# Main_PCB.net
KiCad netlist of a schematic drawn in EAGLE
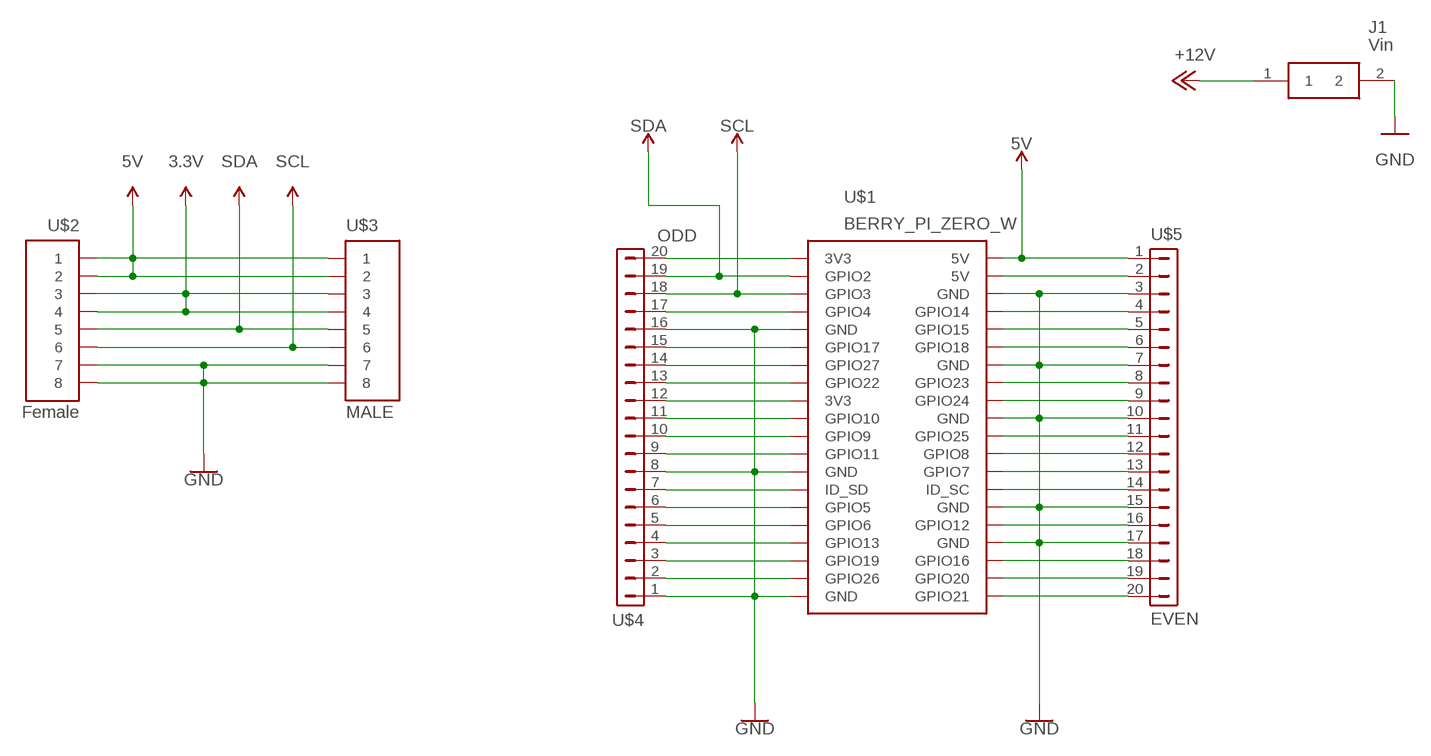
[diagram p0: schematic, sheet 1]
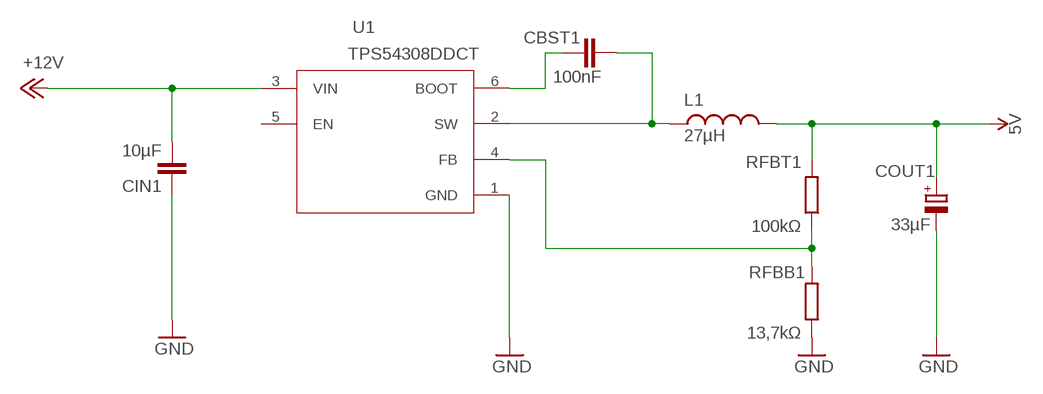
[diagram p1: schematic, sheet 2]
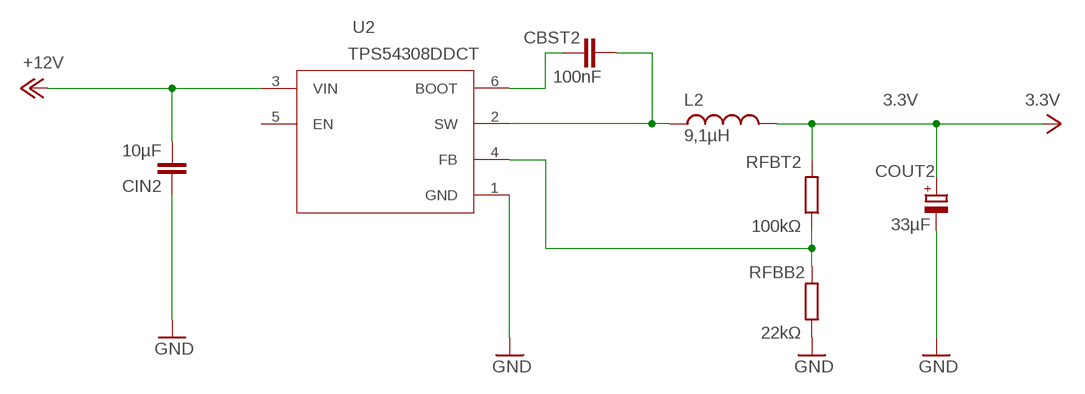
[diagram p2: schematic, sheet 3]

(export (version "E")
  (design (tool "Eeschema 10.0.6"))
  (components
    (comp (ref "CBST2")
      (value "100nF")
      (footprint "eagle-import:C0603")
      (libsource (lib "eagle-import") (part "C-0603"))
    )
    (comp (ref "CIN2")
      (value "10µF")
      (footprint "eagle-import:C1210")
      (libsource (lib "eagle-import") (part "C-1210"))
    )
    (comp (ref "COUT2")
      (value "33µF")
      (footprint "eagle-import:PANASONIC_C")
      (libsource (lib "eagle-import") (part "ELCO_TYPE_C"))
    )
    (comp (ref "L2")
      (value "9,1µH")
      (footprint "eagle-import:WE-PDF")
      (libsource (lib "eagle-import") (part "WE-PDF_1064_7447798910"))
    )
    (comp (ref "RFBB2")
      (value "22kΩ")
      (footprint "eagle-import:R0603")
      (libsource (lib "eagle-import") (part "R-0603"))
    )
    (comp (ref "RFBT2")
      (value "100kΩ")
      (footprint "eagle-import:R0805")
      (libsource (lib "eagle-import") (part "R-0805"))
    )
    (comp (ref "U2")
      (value "TPS54308DDCT")
      (footprint "eagle-import:DDC6")
      (libsource (lib "eagle-import") (part "TPS54308DDCT"))
    )
    (comp (ref "J1")
      (value "Vin")
      (footprint "eagle-import:1990009")
      (fields
        (field (name "MANUFACTURER_PART_NUMBER") "1990009")
        (field (name "MOUSER_PART_NUMBER") "651-1990009")
      )
      (libsource (lib "eagle-import") (part "PUSH_TERMINAL_2WAYS"))
    )
    (comp (ref "U$1")
      (value "BERRY_PI_ZERO_W")
      (footprint "eagle-import:FE20-2")
      (libsource (lib "eagle-import") (part "BERRY_PI_ZERO_W"))
    )
    (comp (ref "U$2")
      (value "Female")
      (footprint "eagle-import:MA04-2")
      (libsource (lib "eagle-import") (part "MODULARCONNECTOR"))
    )
    (comp (ref "U$3")
      (value "MALE")
      (footprint "eagle-import:MA04-2")
      (libsource (lib "eagle-import") (part "MODULARCONNECTOR"))
    )
    (comp (ref "U$4")
      (value "ODD")
      (footprint "eagle-import:FE20")
      (libsource (lib "eagle-import") (part "PARALLELHEADER"))
    )
    (comp (ref "U$5")
      (value "EVEN")
      (footprint "eagle-import:FE20")
      (libsource (lib "eagle-import") (part "PARALLELHEADER"))
    )
    (comp (ref "CBST1")
      (value "100nF")
      (footprint "eagle-import:C0603")
      (libsource (lib "eagle-import") (part "C-0603"))
    )
    (comp (ref "CIN1")
      (value "10µF")
      (footprint "eagle-import:C1210")
      (libsource (lib "eagle-import") (part "C-1210"))
    )
    (comp (ref "COUT1")
      (value "33µF")
      (footprint "eagle-import:PANASONIC_C")
      (libsource (lib "eagle-import") (part "ELCO_TYPE_C"))
    )
    (comp (ref "L1")
      (value "27µH")
      (footprint "eagle-import:WE-PDF")
      (libsource (lib "eagle-import") (part "WE-PDF_1064_7447798910"))
    )
    (comp (ref "RFBB1")
      (value "13,7kΩ")
      (footprint "eagle-import:R0603")
      (libsource (lib "eagle-import") (part "R-0603"))
    )
    (comp (ref "RFBT1")
      (value "100kΩ")
      (footprint "eagle-import:R0805")
      (libsource (lib "eagle-import") (part "R-0805"))
    )
    (comp (ref "U1")
      (value "TPS54308DDCT")
      (footprint "eagle-import:DDC6")
      (libsource (lib "eagle-import") (part "TPS54308DDCT"))
    )
  )
  (nets
    (net (code "1") (name "+12V") (class "Default")
      (node (ref "CIN1") (pin "2") (pinfunction "2_2") (pintype "passive"))
      (node (ref "CIN2") (pin "2") (pinfunction "2_2") (pintype "passive"))
      (node (ref "J1") (pin "1") (pinfunction "1_1") (pintype "bidirectional"))
      (node (ref "U1") (pin "3") (pinfunction "VIN_3") (pintype "passive"))
      (node (ref "U2") (pin "3") (pinfunction "VIN_3") (pintype "passive"))
    )
    (net (code "2") (name "3.3V") (class "Default")
      (node (ref "COUT2") (pin "+") (pinfunction "+_+") (pintype "passive"))
      (node (ref "L2") (pin "2") (pinfunction "2_2") (pintype "passive"))
      (node (ref "RFBT2") (pin "2") (pinfunction "2_2") (pintype "passive"))
      (node (ref "U$2") (pin "3") (pinfunction "3_3") (pintype "input"))
      (node (ref "U$2") (pin "4") (pinfunction "4_4") (pintype "input"))
      (node (ref "U$3") (pin "3") (pinfunction "3_3") (pintype "input"))
      (node (ref "U$3") (pin "4") (pinfunction "4_4") (pintype "input"))
    )
    (net (code "3") (name "5V") (class "Default")
      (node (ref "COUT1") (pin "+") (pinfunction "+_+") (pintype "passive"))
      (node (ref "L1") (pin "2") (pinfunction "2_2") (pintype "passive"))
      (node (ref "RFBT1") (pin "2") (pinfunction "2_2") (pintype "passive"))
      (node (ref "U$1") (pin "2") (pinfunction "5V_2") (pintype "power_in"))
      (node (ref "U$2") (pin "1") (pinfunction "1_1") (pintype "input"))
      (node (ref "U$2") (pin "2") (pinfunction "2_2") (pintype "input"))
      (node (ref "U$3") (pin "1") (pinfunction "1_1") (pintype "input"))
      (node (ref "U$3") (pin "2") (pinfunction "2_2") (pintype "input"))
      (node (ref "U$5") (pin "1") (pinfunction "1_1") (pintype "passive"))
    )
    (net (code "4") (name "GND") (class "Default")
      (node (ref "CIN1") (pin "1") (pinfunction "1_1") (pintype "passive"))
      (node (ref "CIN2") (pin "1") (pinfunction "1_1") (pintype "passive"))
      (node (ref "COUT1") (pin "-") (pinfunction "-_-") (pintype "passive"))
      (node (ref "COUT2") (pin "-") (pinfunction "-_-") (pintype "passive"))
      (node (ref "J1") (pin "2") (pinfunction "2_2") (pintype "bidirectional"))
      (node (ref "RFBB1") (pin "1") (pinfunction "1_1") (pintype "passive"))
      (node (ref "RFBB2") (pin "1") (pinfunction "1_1") (pintype "passive"))
      (node (ref "U$1") (pin "14") (pinfunction "GND_14") (pintype "bidirectional"))
      (node (ref "U$1") (pin "20") (pinfunction "GND_20") (pintype "bidirectional"))
      (node (ref "U$1") (pin "25") (pinfunction "GND_25") (pintype "bidirectional"))
      (node (ref "U$1") (pin "30") (pinfunction "GND_30") (pintype "bidirectional"))
      (node (ref "U$1") (pin "34") (pinfunction "GND_34") (pintype "bidirectional"))
      (node (ref "U$1") (pin "39") (pinfunction "GND_39") (pintype "bidirectional"))
      (node (ref "U$1") (pin "6") (pinfunction "GND_6") (pintype "bidirectional"))
      (node (ref "U$1") (pin "9") (pinfunction "GND_9") (pintype "bidirectional"))
      (node (ref "U$2") (pin "7") (pinfunction "7_7") (pintype "input"))
      (node (ref "U$2") (pin "8") (pinfunction "8_8") (pintype "input"))
      (node (ref "U$3") (pin "7") (pinfunction "7_7") (pintype "input"))
      (node (ref "U$3") (pin "8") (pinfunction "8_8") (pintype "input"))
      (node (ref "U$4") (pin "1") (pinfunction "1_1") (pintype "passive"))
      (node (ref "U$4") (pin "16") (pinfunction "16_16") (pintype "passive"))
      (node (ref "U$4") (pin "8") (pinfunction "8_8") (pintype "passive"))
      (node (ref "U$5") (pin "10") (pinfunction "10_10") (pintype "passive"))
      (node (ref "U$5") (pin "15") (pinfunction "15_15") (pintype "passive"))
      (node (ref "U$5") (pin "17") (pinfunction "17_17") (pintype "passive"))
      (node (ref "U$5") (pin "3") (pinfunction "3_3") (pintype "passive"))
      (node (ref "U$5") (pin "7") (pinfunction "7_7") (pintype "passive"))
      (node (ref "U1") (pin "1") (pinfunction "GND_1") (pintype "passive"))
      (node (ref "U2") (pin "1") (pinfunction "GND_1") (pintype "passive"))
    )
    (net (code "5") (name "Net-(U$1-3V3-Pad1)") (class "Default")
      (node (ref "U$1") (pin "1") (pinfunction "3V3_1") (pintype "input"))
      (node (ref "U$4") (pin "20") (pinfunction "20_20") (pintype "passive"))
    )
    (net (code "6") (name "Net-(U$1-3V3-Pad17)") (class "Default")
      (node (ref "U$1") (pin "17") (pinfunction "3V3_17") (pintype "input"))
      (node (ref "U$4") (pin "12") (pinfunction "12_12") (pintype "passive"))
    )
    (net (code "7") (name "Net-(U$1-5V-Pad4)") (class "Default")
      (node (ref "U$1") (pin "4") (pinfunction "5V_4") (pintype "power_in"))
      (node (ref "U$5") (pin "2") (pinfunction "2_2") (pintype "passive"))
    )
    (net (code "8") (name "Net-(U$1-GPIO4)") (class "Default")
      (node (ref "U$1") (pin "7") (pinfunction "GPIO4_7") (pintype "bidirectional"))
      (node (ref "U$4") (pin "17") (pinfunction "17_17") (pintype "passive"))
    )
    (net (code "9") (name "Net-(U$1-GPIO5)") (class "Default")
      (node (ref "U$1") (pin "29") (pinfunction "GPIO5_29") (pintype "bidirectional"))
      (node (ref "U$4") (pin "6") (pinfunction "6_6") (pintype "passive"))
    )
    (net (code "10") (name "Net-(U$1-GPIO6)") (class "Default")
      (node (ref "U$1") (pin "31") (pinfunction "GPIO6_31") (pintype "bidirectional"))
      (node (ref "U$4") (pin "5") (pinfunction "5_5") (pintype "passive"))
    )
    (net (code "11") (name "Net-(U$1-GPIO7)") (class "Default")
      (node (ref "U$1") (pin "26") (pinfunction "GPIO7_26") (pintype "bidirectional"))
      (node (ref "U$5") (pin "13") (pinfunction "13_13") (pintype "passive"))
    )
    (net (code "12") (name "Net-(U$1-GPIO8)") (class "Default")
      (node (ref "U$1") (pin "24") (pinfunction "GPIO8_24") (pintype "bidirectional"))
      (node (ref "U$5") (pin "12") (pinfunction "12_12") (pintype "passive"))
    )
    (net (code "13") (name "Net-(U$1-GPIO9)") (class "Default")
      (node (ref "U$1") (pin "21") (pinfunction "GPIO9_21") (pintype "bidirectional"))
      (node (ref "U$4") (pin "10") (pinfunction "10_10") (pintype "passive"))
    )
    (net (code "14") (name "Net-(U$1-GPIO10)") (class "Default")
      (node (ref "U$1") (pin "19") (pinfunction "GPIO10_19") (pintype "bidirectional"))
      (node (ref "U$4") (pin "11") (pinfunction "11_11") (pintype "passive"))
    )
    (net (code "15") (name "Net-(U$1-GPIO11)") (class "Default")
      (node (ref "U$1") (pin "23") (pinfunction "GPIO11_23") (pintype "bidirectional"))
      (node (ref "U$4") (pin "9") (pinfunction "9_9") (pintype "passive"))
    )
    (net (code "16") (name "Net-(U$1-GPIO12)") (class "Default")
      (node (ref "U$1") (pin "32") (pinfunction "GPIO12_32") (pintype "bidirectional"))
      (node (ref "U$5") (pin "16") (pinfunction "16_16") (pintype "passive"))
    )
    (net (code "17") (name "Net-(U$1-GPIO13)") (class "Default")
      (node (ref "U$1") (pin "33") (pinfunction "GPIO13_33") (pintype "bidirectional"))
      (node (ref "U$4") (pin "4") (pinfunction "4_4") (pintype "passive"))
    )
    (net (code "18") (name "Net-(U$1-GPIO14)") (class "Default")
      (node (ref "U$1") (pin "8") (pinfunction "GPIO14_8") (pintype "bidirectional"))
      (node (ref "U$5") (pin "4") (pinfunction "4_4") (pintype "passive"))
    )
    (net (code "19") (name "Net-(U$1-GPIO15)") (class "Default")
      (node (ref "U$1") (pin "10") (pinfunction "GPIO15_10") (pintype "bidirectional"))
      (node (ref "U$5") (pin "5") (pinfunction "5_5") (pintype "passive"))
    )
    (net (code "20") (name "Net-(U$1-GPIO16)") (class "Default")
      (node (ref "U$1") (pin "36") (pinfunction "GPIO16_36") (pintype "bidirectional"))
      (node (ref "U$5") (pin "18") (pinfunction "18_18") (pintype "passive"))
    )
    (net (code "21") (name "Net-(U$1-GPIO17)") (class "Default")
      (node (ref "U$1") (pin "11") (pinfunction "GPIO17_11") (pintype "bidirectional"))
      (node (ref "U$4") (pin "15") (pinfunction "15_15") (pintype "passive"))
    )
    (net (code "22") (name "Net-(U$1-GPIO18)") (class "Default")
      (node (ref "U$1") (pin "12") (pinfunction "GPIO18_12") (pintype "bidirectional"))
      (node (ref "U$5") (pin "6") (pinfunction "6_6") (pintype "passive"))
    )
    (net (code "23") (name "Net-(U$1-GPIO19)") (class "Default")
      (node (ref "U$1") (pin "35") (pinfunction "GPIO19_35") (pintype "bidirectional"))
      (node (ref "U$4") (pin "3") (pinfunction "3_3") (pintype "passive"))
    )
    (net (code "24") (name "Net-(U$1-GPIO20)") (class "Default")
      (node (ref "U$1") (pin "38") (pinfunction "GPIO20_38") (pintype "bidirectional"))
      (node (ref "U$5") (pin "19") (pinfunction "19_19") (pintype "passive"))
    )
    (net (code "25") (name "Net-(U$1-GPIO21)") (class "Default")
      (node (ref "U$1") (pin "40") (pinfunction "GPIO21_40") (pintype "bidirectional"))
      (node (ref "U$5") (pin "20") (pinfunction "20_20") (pintype "passive"))
    )
    (net (code "26") (name "Net-(U$1-GPIO22)") (class "Default")
      (node (ref "U$1") (pin "15") (pinfunction "GPIO22_15") (pintype "bidirectional"))
      (node (ref "U$4") (pin "13") (pinfunction "13_13") (pintype "passive"))
    )
    (net (code "27") (name "Net-(U$1-GPIO23)") (class "Default")
      (node (ref "U$1") (pin "16") (pinfunction "GPIO23_16") (pintype "bidirectional"))
      (node (ref "U$5") (pin "8") (pinfunction "8_8") (pintype "passive"))
    )
    (net (code "28") (name "Net-(U$1-GPIO24)") (class "Default")
      (node (ref "U$1") (pin "18") (pinfunction "GPIO24_18") (pintype "bidirectional"))
      (node (ref "U$5") (pin "9") (pinfunction "9_9") (pintype "passive"))
    )
    (net (code "29") (name "Net-(U$1-GPIO25)") (class "Default")
      (node (ref "U$1") (pin "22") (pinfunction "GPIO25_22") (pintype "bidirectional"))
      (node (ref "U$5") (pin "11") (pinfunction "11_11") (pintype "passive"))
    )
    (net (code "30") (name "Net-(U$1-GPIO26)") (class "Default")
      (node (ref "U$1") (pin "37") (pinfunction "GPIO26_37") (pintype "bidirectional"))
      (node (ref "U$4") (pin "2") (pinfunction "2_2") (pintype "passive"))
    )
    (net (code "31") (name "Net-(U$1-GPIO27)") (class "Default")
      (node (ref "U$1") (pin "13") (pinfunction "GPIO27_13") (pintype "bidirectional"))
      (node (ref "U$4") (pin "14") (pinfunction "14_14") (pintype "passive"))
    )
    (net (code "32") (name "Net-(U$1-ID_SC)") (class "Default")
      (node (ref "U$1") (pin "28") (pinfunction "ID_SC_28") (pintype "bidirectional"))
      (node (ref "U$5") (pin "14") (pinfunction "14_14") (pintype "passive"))
    )
    (net (code "33") (name "Net-(U$1-ID_SD)") (class "Default")
      (node (ref "U$1") (pin "27") (pinfunction "ID_SD_27") (pintype "bidirectional"))
      (node (ref "U$4") (pin "7") (pinfunction "7_7") (pintype "passive"))
    )
    (net (code "34") (name "Net-(U1-BOOT)") (class "Default")
      (node (ref "CBST1") (pin "1") (pinfunction "1_1") (pintype "passive"))
      (node (ref "U1") (pin "6") (pinfunction "BOOT_6") (pintype "passive"))
    )
    (net (code "35") (name "Net-(U1-FB)") (class "Default")
      (node (ref "RFBB1") (pin "2") (pinfunction "2_2") (pintype "passive"))
      (node (ref "RFBT1") (pin "1") (pinfunction "1_1") (pintype "passive"))
      (node (ref "U1") (pin "4") (pinfunction "FB_4") (pintype "passive"))
    )
    (net (code "36") (name "Net-(U1-SW)") (class "Default")
      (node (ref "CBST1") (pin "2") (pinfunction "2_2") (pintype "passive"))
      (node (ref "L1") (pin "1") (pinfunction "1_1") (pintype "passive"))
      (node (ref "U1") (pin "2") (pinfunction "SW_2") (pintype "passive"))
    )
    (net (code "37") (name "Net-(U2-BOOT)") (class "Default")
      (node (ref "CBST2") (pin "1") (pinfunction "1_1") (pintype "passive"))
      (node (ref "U2") (pin "6") (pinfunction "BOOT_6") (pintype "passive"))
    )
    (net (code "38") (name "Net-(U2-FB)") (class "Default")
      (node (ref "RFBB2") (pin "2") (pinfunction "2_2") (pintype "passive"))
      (node (ref "RFBT2") (pin "1") (pinfunction "1_1") (pintype "passive"))
      (node (ref "U2") (pin "4") (pinfunction "FB_4") (pintype "passive"))
    )
    (net (code "39") (name "Net-(U2-SW)") (class "Default")
      (node (ref "CBST2") (pin "2") (pinfunction "2_2") (pintype "passive"))
      (node (ref "L2") (pin "1") (pinfunction "1_1") (pintype "passive"))
      (node (ref "U2") (pin "2") (pinfunction "SW_2") (pintype "passive"))
    )
    (net (code "40") (name "SCL") (class "Default")
      (node (ref "U$1") (pin "5") (pinfunction "GPIO3_5") (pintype "bidirectional"))
      (node (ref "U$2") (pin "6") (pinfunction "6_6") (pintype "input"))
      (node (ref "U$3") (pin "6") (pinfunction "6_6") (pintype "input"))
      (node (ref "U$4") (pin "18") (pinfunction "18_18") (pintype "passive"))
    )
    (net (code "41") (name "SDA") (class "Default")
      (node (ref "U$1") (pin "3") (pinfunction "GPIO2_3") (pintype "bidirectional"))
      (node (ref "U$2") (pin "5") (pinfunction "5_5") (pintype "input"))
      (node (ref "U$3") (pin "5") (pinfunction "5_5") (pintype "input"))
      (node (ref "U$4") (pin "19") (pinfunction "19_19") (pintype "passive"))
    )
    (net (code "42") (name "unconnected-(U1-EN-Pad5)") (class "Default")
      (node (ref "U1") (pin "5") (pinfunction "EN_5") (pintype "passive"))
    )
    (net (code "43") (name "unconnected-(U2-EN-Pad5)") (class "Default")
      (node (ref "U2") (pin "5") (pinfunction "EN_5") (pintype "passive"))
    )
  )
)
